# Power.net
KiCad netlist of a schematic drawn in Altium Designer
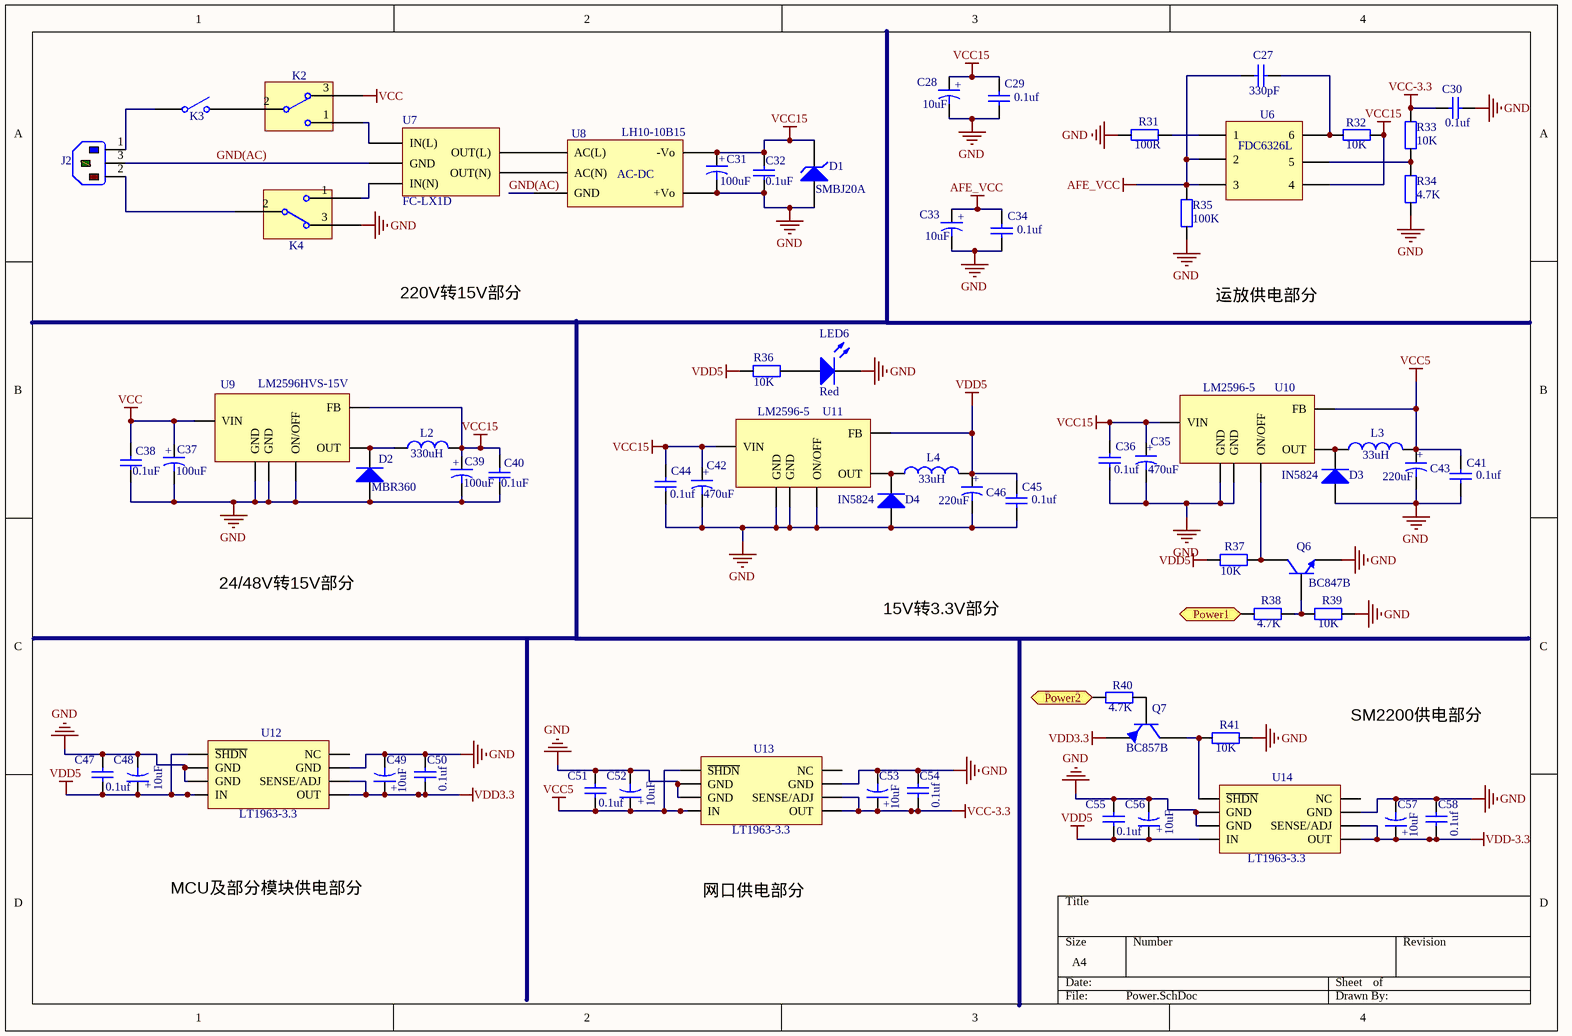
[diagram p0: Power.SchDoc]

(export (version "E")
  (design (tool "Eeschema 10.0.6"))
  (components
    (comp (ref "C27")
      (value "330pF")
      (footprint "0603")
      (fields (field (name "Comment") "Capacitor-0805"))
      (libsource (lib "集成库—大岐") (part "Capacitor-0805"))
    )
    (comp (ref "C28")
      (value "10uF")
      (footprint "3528")
      (fields (field (name "ALTIUM_UNNAMED_1") "+") (field (name "Comment") "电解电容"))
      (libsource (lib "原理图库") (part "电解电容"))
    )
    (comp (ref "C29")
      (value "0.1uf")
      (footprint "0805")
      (fields (field (name "Comment") "Capacitor-0805"))
      (libsource (lib "集成库—大岐") (part "Capacitor-0805"))
    )
    (comp (ref "C30")
      (value "0.1uf")
      (footprint "0603")
      (fields (field (name "Comment") "Capacitor-0805"))
      (libsource (lib "集成库—大岐") (part "Capacitor-0805"))
    )
    (comp (ref "C31")
      (value "100uF")
      (footprint "贴片铝电容-8*10.3")
      (fields (field (name "ALTIUM_UNNAMED_1") "+") (field (name "Comment") "电解电容"))
      (libsource (lib "原理图库") (part "电解电容"))
    )
    (comp (ref "C32")
      (value "0.1uF")
      (footprint "0805")
      (fields (field (name "Comment") "Capacitor-0805"))
      (libsource (lib "原理图库") (part "Capacitor-0805"))
    )
    (comp (ref "C33")
      (value "10uF")
      (footprint "3528")
      (fields (field (name "ALTIUM_UNNAMED_1") "+") (field (name "Comment") "电解电容"))
      (libsource (lib "原理图库") (part "电解电容"))
    )
    (comp (ref "C34")
      (value "0.1uf")
      (footprint "0805")
      (fields (field (name "Comment") "Capacitor-0805"))
      (libsource (lib "集成库—大岐") (part "Capacitor-0805"))
    )
    (comp (ref "C35")
      (value "470uF")
      (footprint "贴片铝电容-10*10")
      (fields (field (name "ALTIUM_UNNAMED_1") "+") (field (name "Comment") "电解电容"))
      (libsource (lib "集成库—大岐") (part "电解电容"))
    )
    (comp (ref "C36")
      (value "0.1uf")
      (footprint "0805")
      (fields (field (name "Comment") "Capacitor-0805"))
      (libsource (lib "集成库—大岐") (part "Capacitor-0805"))
    )
    (comp (ref "C37")
      (value "100uF")
      (footprint "贴片铝电容-8*10.3")
      (fields (field (name "ALTIUM_UNNAMED_1") "+") (field (name "Comment") "电解电容"))
      (libsource (lib "原理图库") (part "电解电容"))
    )
    (comp (ref "C38")
      (value "0.1uF")
      (footprint "0805")
      (fields (field (name "Comment") "Capacitor-0805"))
      (libsource (lib "原理图库") (part "Capacitor-0805"))
    )
    (comp (ref "C39")
      (value "100uF")
      (footprint "贴片铝电容-8*10.3")
      (fields (field (name "ALTIUM_UNNAMED_1") "+") (field (name "Comment") "电解电容"))
      (libsource (lib "原理图库") (part "电解电容"))
    )
    (comp (ref "C40")
      (value "0.1uF")
      (footprint "0805")
      (fields (field (name "Comment") "Capacitor-0805"))
      (libsource (lib "原理图库") (part "Capacitor-0805"))
    )
    (comp (ref "C41")
      (value "0.1uf")
      (footprint "0805")
      (fields (field (name "Comment") "Capacitor-0805"))
      (libsource (lib "集成库—大岐") (part "Capacitor-0805"))
    )
    (comp (ref "C42")
      (value "470uF")
      (footprint "贴片铝电容-10*10")
      (fields (field (name "ALTIUM_UNNAMED_1") "+") (field (name "Comment") "电解电容"))
      (libsource (lib "集成库—大岐") (part "电解电容"))
    )
    (comp (ref "C43")
      (value "220uF")
      (footprint "贴片铝电容-8*10.3")
      (fields (field (name "ALTIUM_UNNAMED_1") "+") (field (name "Comment") "电解电容"))
      (libsource (lib "集成库—大岐") (part "电解电容"))
    )
    (comp (ref "C44")
      (value "0.1uf")
      (footprint "0805")
      (fields (field (name "Comment") "Capacitor-0805"))
      (libsource (lib "集成库—大岐") (part "Capacitor-0805"))
    )
    (comp (ref "C45")
      (value "0.1uf")
      (footprint "0805")
      (fields (field (name "Comment") "Capacitor-0805"))
      (libsource (lib "集成库—大岐") (part "Capacitor-0805"))
    )
    (comp (ref "C46")
      (value "220uF")
      (footprint "贴片铝电容-8*10.3")
      (fields (field (name "ALTIUM_UNNAMED_1") "+") (field (name "Comment") "电解电容"))
      (libsource (lib "集成库—大岐") (part "电解电容"))
    )
    (comp (ref "C47")
      (value "0.1uf")
      (footprint "0805")
      (fields (field (name "Comment") "Capacitor-0805"))
      (libsource (lib "集成库—大岐") (part "Capacitor-0805"))
    )
    (comp (ref "C48")
      (value "10uF")
      (footprint "钽电容1206（A3216）")
      (fields (field (name "ALTIUM_UNNAMED_1") "+") (field (name "Comment") "电解电容"))
      (libsource (lib "集成库—大岐") (part "电解电容"))
    )
    (comp (ref "C49")
      (value "10uF")
      (footprint "钽电容1206（A3216）")
      (fields (field (name "ALTIUM_UNNAMED_1") "+") (field (name "Comment") "电解电容"))
      (libsource (lib "集成库—大岐") (part "电解电容"))
    )
    (comp (ref "C50")
      (value "0.1uf")
      (footprint "0805")
      (fields (field (name "Comment") "Capacitor-0805"))
      (libsource (lib "集成库—大岐") (part "Capacitor-0805"))
    )
    (comp (ref "C51")
      (value "0.1uf")
      (footprint "0805")
      (fields (field (name "Comment") "Capacitor-0805"))
      (libsource (lib "集成库—大岐") (part "Capacitor-0805"))
    )
    (comp (ref "C52")
      (value "10uF")
      (footprint "钽电容1206（A3216）")
      (fields (field (name "ALTIUM_UNNAMED_1") "+") (field (name "Comment") "电解电容"))
      (libsource (lib "集成库—大岐") (part "电解电容"))
    )
    (comp (ref "C53")
      (value "10uF")
      (footprint "钽电容1206（A3216）")
      (fields (field (name "ALTIUM_UNNAMED_1") "+") (field (name "Comment") "电解电容"))
      (libsource (lib "集成库—大岐") (part "电解电容"))
    )
    (comp (ref "C54")
      (value "0.1uf")
      (footprint "0805")
      (fields (field (name "Comment") "Capacitor-0805"))
      (libsource (lib "集成库—大岐") (part "Capacitor-0805"))
    )
    (comp (ref "C55")
      (value "0.1uf")
      (footprint "0805")
      (fields (field (name "Comment") "Capacitor-0805"))
      (libsource (lib "集成库—大岐") (part "Capacitor-0805"))
    )
    (comp (ref "C56")
      (value "10uF")
      (footprint "钽电容1206（A3216）")
      (fields (field (name "ALTIUM_UNNAMED_1") "+") (field (name "Comment") "电解电容"))
      (libsource (lib "集成库—大岐") (part "电解电容"))
    )
    (comp (ref "C57")
      (value "10uF")
      (footprint "钽电容1206（A3216）")
      (fields (field (name "ALTIUM_UNNAMED_1") "+") (field (name "Comment") "电解电容"))
      (libsource (lib "集成库—大岐") (part "电解电容"))
    )
    (comp (ref "C58")
      (value "0.1uf")
      (footprint "0805")
      (fields (field (name "Comment") "Capacitor-0805"))
      (libsource (lib "集成库—大岐") (part "Capacitor-0805"))
    )
    (comp (ref "D1")
      (value "SMBJ20A")
      (footprint "SMBJ20A")
      (fields (field (name "NAME") "SMBJ20A"))
      (libsource (lib "原理图库") (part "SMBJ20A"))
    )
    (comp (ref "D2")
      (value "MBR360")
      (footprint "IN5824")
      (fields (field (name "Comment") "IN5824"))
      (libsource (lib "原理图库") (part "IN5824"))
    )
    (comp (ref "D3")
      (value "IN5824")
      (footprint "IN5824")
      (fields (field (name "ALTIUM_UNNAMED_1") "IN5824"))
      (libsource (lib "集成库—大岐") (part "IN5824"))
    )
    (comp (ref "D4")
      (value "IN5824")
      (footprint "IN5824")
      (fields (field (name "ALTIUM_UNNAMED_1") "IN5824"))
      (libsource (lib "集成库—大岐") (part "IN5824"))
    )
    (comp (ref "J2") (value "三脚航空插头") (footprint "三脚航空插头") (libsource (lib "原理图库") (part "三脚航空插头")))
    (comp (ref "K2") (value "选择开关") (footprint "选择开关") (libsource (lib "") (part "选择开关_1")))
    (comp (ref "K3") (value "开关") (footprint "T型接头") (libsource (lib "原理图库") (part "开关")))
    (comp (ref "K4") (value "选择开关") (footprint "选择开关") (libsource (lib "原理图库") (part "选择开关")))
    (comp (ref "L2")
      (value "330uH")
      (footprint "Inductor(7.8*7*5)")
      (fields (field (name "Comment") "Inductor"))
      (libsource (lib "原理图库") (part "Inductor"))
    )
    (comp (ref "L3")
      (value "33uH")
      (footprint "SLF6025   电感")
      (fields (field (name "Comment") "Inductor"))
      (libsource (lib "集成库—大岐") (part "Inductor"))
    )
    (comp (ref "L4")
      (value "33uH")
      (footprint "SLF6025   电感")
      (fields (field (name "Comment") "Inductor"))
      (libsource (lib "集成库—大岐") (part "Inductor"))
    )
    (comp (ref "LED6")
      (value "LED")
      (footprint "外插小灯")
      (fields (field (name "COLOR") "Red"))
      (libsource (lib "原理图库") (part "LED"))
    )
    (comp (ref "Q6")
      (value "BC847")
      (footprint "BC847B")
      (fields (field (name "NAME") "BC847B"))
      (libsource (lib "原理图库") (part "BC847"))
    )
    (comp (ref "Q7")
      (value "BC587B")
      (footprint "BC847B")
      (fields (field (name "NAME") "BC857B"))
      (libsource (lib "原理图库") (part "BC587B"))
    )
    (comp (ref "R31")
      (value "100R")
      (footprint "0603")
      (fields (field (name "Comment") "Resistor-0603"))
      (libsource (lib "") (part "Resistor-0603_2"))
    )
    (comp (ref "R32")
      (value "10K")
      (footprint "0603")
      (fields (field (name "Comment") "Resistor-0603"))
      (libsource (lib "原理图库") (part "Resistor-0603"))
    )
    (comp (ref "R33")
      (value "10K")
      (footprint "0603")
      (fields (field (name "Comment") "Resistor-0603"))
      (libsource (lib "") (part "Resistor-0603_1"))
    )
    (comp (ref "R34")
      (value "4.7K")
      (footprint "0603")
      (fields (field (name "Comment") "Resistor-0603"))
      (libsource (lib "") (part "Resistor-0603_1"))
    )
    (comp (ref "R35")
      (value "100K")
      (footprint "0603")
      (fields (field (name "Comment") "Resistor-0603"))
      (libsource (lib "") (part "Resistor-0603_1"))
    )
    (comp (ref "R36")
      (value "10K")
      (footprint "0603")
      (fields (field (name "Comment") "Resistor-0603"))
      (libsource (lib "原理图库") (part "Resistor-0603"))
    )
    (comp (ref "R37")
      (value "10K")
      (footprint "0603")
      (fields (field (name "Comment") "Resistor-0603"))
      (libsource (lib "") (part "Resistor-0603_2"))
    )
    (comp (ref "R38")
      (value "4.7K")
      (footprint "0603")
      (fields (field (name "Comment") "Resistor-0603"))
      (libsource (lib "原理图库") (part "Resistor-0603"))
    )
    (comp (ref "R39")
      (value "10K")
      (footprint "0603")
      (fields (field (name "Comment") "Resistor-0603"))
      (libsource (lib "原理图库") (part "Resistor-0603"))
    )
    (comp (ref "R40")
      (value "4.7K")
      (footprint "0603")
      (fields (field (name "Comment") "Resistor-0603"))
      (libsource (lib "原理图库") (part "Resistor-0603"))
    )
    (comp (ref "R41")
      (value "10K")
      (footprint "0603")
      (fields (field (name "Comment") "Resistor-0603"))
      (libsource (lib "原理图库") (part "Resistor-0603"))
    )
    (comp (ref "U6")
      (value "FDC6326L")
      (footprint "FDC6326L")
      (fields (field (name "NAME") "FDC6326L"))
      (libsource (lib "原理图库") (part "FDC6326L"))
    )
    (comp (ref "U7")
      (value "FC-LX1D")
      (footprint "FC-LX1D")
      (fields (field (name "NAME") "FC-LX1D"))
      (libsource (lib "原理图库") (part "FC-LX1D"))
    )
    (comp (ref "U8")
      (value "LH10-10B15")
      (footprint "LH10-10B15")
      (fields (field (name "DESCRIBE") "AC-DC") (field (name "NAME") "LH10-10B15"))
      (libsource (lib "原理图库") (part "LH10-10B15"))
    )
    (comp (ref "U9")
      (value "LM2596HVS-15V")
      (footprint "LM2596")
      (fields (field (name "Comment") "LM2596"))
      (libsource (lib "原理图库") (part "LM2596"))
    )
    (comp (ref "U10")
      (value "LM2596")
      (footprint "LM2596")
      (fields (field (name "ALTIUM_UNNAMED_1") "LM2596-5"))
      (libsource (lib "集成库—大岐") (part "LM2596"))
    )
    (comp (ref "U11")
      (value "LM2596")
      (footprint "LM2596")
      (fields (field (name "ALTIUM_UNNAMED_1") "LM2596-5"))
      (libsource (lib "集成库—大岐") (part "LM2596"))
    )
    (comp (ref "U12")
      (value "LT1963")
      (footprint "LT1963")
      (fields (field (name "ALTIUM_UNNAMED_1") "LT1963-3.3"))
      (libsource (lib "集成库—大岐") (part "LT1963"))
    )
    (comp (ref "U13")
      (value "LT1963")
      (footprint "LT1963")
      (fields (field (name "ALTIUM_UNNAMED_1") "LT1963-3.3"))
      (libsource (lib "集成库—大岐") (part "LT1963"))
    )
    (comp (ref "U14")
      (value "LT1963")
      (footprint "LT1963")
      (fields (field (name "ALTIUM_UNNAMED_1") "LT1963-3.3"))
      (libsource (lib "集成库—大岐") (part "LT1963"))
    )
  )
  (nets
    (net (code "1") (name "/GND(AC)") (class "Default")
      (node (ref "J2") (pin "3") (pinfunction "3_3") (pintype "passive"))
      (node (ref "U7") (pin "1") (pinfunction "GND_1") (pintype "passive"))
      (node (ref "U8") (pin "1") (pinfunction "GND_1") (pintype "passive"))
    )
    (net (code "2") (name "/Power1") (class "Default")
      (node (ref "R38") (pin "2") (pinfunction "2_2") (pintype "passive"))
    )
    (net (code "3") (name "/Power2") (class "Default")
      (node (ref "R40") (pin "2") (pinfunction "2_2") (pintype "passive"))
    )
    (net (code "4") (name "AFE_VCC") (class "Default")
      (node (ref "C27") (pin "2") (pinfunction "2_2") (pintype "passive"))
      (node (ref "C33") (pin "2") (pinfunction "2_2") (pintype "passive"))
      (node (ref "C34") (pin "2") (pinfunction "2_2") (pintype "passive"))
      (node (ref "R35") (pin "2") (pinfunction "2_2") (pintype "passive"))
      (node (ref "U6") (pin "2") (pinfunction "2_2") (pintype "passive"))
      (node (ref "U6") (pin "3") (pinfunction "3_3") (pintype "passive"))
    )
    (net (code "5") (name "GND") (class "Default")
      (node (ref "C28") (pin "1") (pinfunction "1_1") (pintype "passive"))
      (node (ref "C29") (pin "1") (pinfunction "1_1") (pintype "passive"))
      (node (ref "C30") (pin "1") (pinfunction "1_1") (pintype "passive"))
      (node (ref "C31") (pin "1") (pinfunction "1_1") (pintype "passive"))
      (node (ref "C32") (pin "1") (pinfunction "1_1") (pintype "passive"))
      (node (ref "C33") (pin "1") (pinfunction "1_1") (pintype "passive"))
      (node (ref "C34") (pin "1") (pinfunction "1_1") (pintype "passive"))
      (node (ref "C35") (pin "1") (pinfunction "1_1") (pintype "passive"))
      (node (ref "C36") (pin "1") (pinfunction "1_1") (pintype "passive"))
      (node (ref "C37") (pin "1") (pinfunction "1_1") (pintype "passive"))
      (node (ref "C38") (pin "1") (pinfunction "1_1") (pintype "passive"))
      (node (ref "C39") (pin "1") (pinfunction "1_1") (pintype "passive"))
      (node (ref "C40") (pin "1") (pinfunction "1_1") (pintype "passive"))
      (node (ref "C41") (pin "1") (pinfunction "1_1") (pintype "passive"))
      (node (ref "C42") (pin "1") (pinfunction "1_1") (pintype "passive"))
      (node (ref "C43") (pin "1") (pinfunction "1_1") (pintype "passive"))
      (node (ref "C44") (pin "1") (pinfunction "1_1") (pintype "passive"))
      (node (ref "C45") (pin "1") (pinfunction "1_1") (pintype "passive"))
      (node (ref "C46") (pin "1") (pinfunction "1_1") (pintype "passive"))
      (node (ref "C47") (pin "2") (pinfunction "2_2") (pintype "passive"))
      (node (ref "C48") (pin "1") (pinfunction "1_1") (pintype "passive"))
      (node (ref "C49") (pin "1") (pinfunction "1_1") (pintype "passive"))
      (node (ref "C50") (pin "2") (pinfunction "2_2") (pintype "passive"))
      (node (ref "C51") (pin "2") (pinfunction "2_2") (pintype "passive"))
      (node (ref "C52") (pin "1") (pinfunction "1_1") (pintype "passive"))
      (node (ref "C53") (pin "1") (pinfunction "1_1") (pintype "passive"))
      (node (ref "C54") (pin "2") (pinfunction "2_2") (pintype "passive"))
      (node (ref "C55") (pin "2") (pinfunction "2_2") (pintype "passive"))
      (node (ref "C56") (pin "1") (pinfunction "1_1") (pintype "passive"))
      (node (ref "C57") (pin "1") (pinfunction "1_1") (pintype "passive"))
      (node (ref "C58") (pin "2") (pinfunction "2_2") (pintype "passive"))
      (node (ref "D1") (pin "1") (pinfunction "A_1") (pintype "passive"))
      (node (ref "D2") (pin "1") (pinfunction "A_1") (pintype "passive"))
      (node (ref "D3") (pin "1") (pinfunction "A_1") (pintype "passive"))
      (node (ref "D4") (pin "1") (pinfunction "A_1") (pintype "passive"))
      (node (ref "K4") (pin "3") (pinfunction "3_3") (pintype "passive"))
      (node (ref "LED6") (pin "2") (pinfunction "2_2") (pintype "passive"))
      (node (ref "Q6") (pin "1") (pinfunction "E_1") (pintype "passive"))
      (node (ref "R31") (pin "1") (pinfunction "1_1") (pintype "passive"))
      (node (ref "R34") (pin "1") (pinfunction "1_1") (pintype "passive"))
      (node (ref "R35") (pin "1") (pinfunction "1_1") (pintype "passive"))
      (node (ref "R39") (pin "1") (pinfunction "1_1") (pintype "passive"))
      (node (ref "R41") (pin "1") (pinfunction "1_1") (pintype "passive"))
      (node (ref "U10") (pin "3") (pinfunction "GND_3") (pintype "passive"))
      (node (ref "U10") (pin "6") (pinfunction "GND_6") (pintype "passive"))
      (node (ref "U11") (pin "3") (pinfunction "GND_3") (pintype "passive"))
      (node (ref "U11") (pin "5") (pinfunction "ON/OFF_5") (pintype "passive"))
      (node (ref "U11") (pin "6") (pinfunction "GND_6") (pintype "passive"))
      (node (ref "U12") (pin "3") (pinfunction "GND_3") (pintype "passive"))
      (node (ref "U12") (pin "6") (pinfunction "GND_6") (pintype "passive"))
      (node (ref "U12") (pin "7") (pinfunction "GND_7") (pintype "passive"))
      (node (ref "U13") (pin "3") (pinfunction "GND_3") (pintype "passive"))
      (node (ref "U13") (pin "6") (pinfunction "GND_6") (pintype "passive"))
      (node (ref "U13") (pin "7") (pinfunction "GND_7") (pintype "passive"))
      (node (ref "U14") (pin "3") (pinfunction "GND_3") (pintype "passive"))
      (node (ref "U14") (pin "6") (pinfunction "GND_6") (pintype "passive"))
      (node (ref "U14") (pin "7") (pinfunction "GND_7") (pintype "passive"))
      (node (ref "U8") (pin "8") (pinfunction "+Vo_8") (pintype "passive"))
      (node (ref "U9") (pin "3") (pinfunction "GND_3") (pintype "passive"))
      (node (ref "U9") (pin "5") (pinfunction "ON/OFF_5") (pintype "passive"))
      (node (ref "U9") (pin "6") (pinfunction "GND_6") (pintype "passive"))
    )
    (net (code "6") (name "Net-(C27-Pad1)") (class "Default")
      (node (ref "C27") (pin "1") (pinfunction "1_1") (pintype "passive"))
      (node (ref "R32") (pin "2") (pinfunction "2_2") (pintype "passive"))
      (node (ref "U6") (pin "6") (pinfunction "6_6") (pintype "passive"))
    )
    (net (code "7") (name "Net-(D2-K)") (class "Default")
      (node (ref "D2") (pin "2") (pinfunction "K_2") (pintype "passive"))
      (node (ref "L2") (pin "1") (pinfunction "1_1") (pintype "passive"))
      (node (ref "U9") (pin "2") (pinfunction "OUT_2") (pintype "passive"))
    )
    (net (code "8") (name "Net-(D3-K)") (class "Default")
      (node (ref "D3") (pin "2") (pinfunction "K_2") (pintype "passive"))
      (node (ref "L3") (pin "1") (pinfunction "1_1") (pintype "passive"))
      (node (ref "U10") (pin "2") (pinfunction "OUT_2") (pintype "passive"))
    )
    (net (code "9") (name "Net-(D4-K)") (class "Default")
      (node (ref "D4") (pin "2") (pinfunction "K_2") (pintype "passive"))
      (node (ref "L4") (pin "1") (pinfunction "1_1") (pintype "passive"))
      (node (ref "U11") (pin "2") (pinfunction "OUT_2") (pintype "passive"))
    )
    (net (code "10") (name "Net-(J2-Pad2)") (class "Default")
      (node (ref "J2") (pin "2") (pinfunction "2_2") (pintype "passive"))
      (node (ref "K4") (pin "2") (pinfunction "2_2") (pintype "passive"))
    )
    (net (code "11") (name "Net-(K3-COMMON)") (class "Default")
      (node (ref "J2") (pin "1") (pinfunction "1_1") (pintype "passive"))
      (node (ref "K3") (pin "1") (pinfunction "COMMON_1") (pintype "passive"))
    )
    (net (code "12") (name "Net-(K3-NO)") (class "Default")
      (node (ref "K2") (pin "2") (pinfunction "2_2") (pintype "passive"))
      (node (ref "K3") (pin "2") (pinfunction "NO_2") (pintype "passive"))
    )
    (net (code "13") (name "Net-(LED6-A)") (class "Default")
      (node (ref "LED6") (pin "1") (pinfunction "A_1") (pintype "passive"))
      (node (ref "R36") (pin "1") (pinfunction "1_1") (pintype "passive"))
    )
    (net (code "14") (name "Net-(Q6-B)") (class "Default")
      (node (ref "Q6") (pin "2") (pinfunction "B_2") (pintype "passive"))
      (node (ref "R38") (pin "1") (pinfunction "1_1") (pintype "passive"))
      (node (ref "R39") (pin "2") (pinfunction "2_2") (pintype "passive"))
    )
    (net (code "15") (name "Net-(Q6-C)") (class "Default")
      (node (ref "Q6") (pin "3") (pinfunction "C_3") (pintype "passive"))
      (node (ref "R37") (pin "2") (pinfunction "2_2") (pintype "passive"))
      (node (ref "U10") (pin "5") (pinfunction "ON/OFF_5") (pintype "passive"))
    )
    (net (code "16") (name "Net-(Q7-B)") (class "Default")
      (node (ref "Q7") (pin "2") (pinfunction "B_2") (pintype "passive"))
      (node (ref "R40") (pin "1") (pinfunction "1_1") (pintype "passive"))
    )
    (net (code "17") (name "Net-(Q7-C)") (class "Default")
      (node (ref "Q7") (pin "3") (pinfunction "C_3") (pintype "passive"))
      (node (ref "R41") (pin "2") (pinfunction "2_2") (pintype "passive"))
      (node (ref "U14") (pin "5") (pinfunction "~{SHDN}_5") (pintype "passive"))
    )
    (net (code "18") (name "Net-(R31-Pad2)") (class "Default")
      (node (ref "R31") (pin "2") (pinfunction "2_2") (pintype "passive"))
      (node (ref "U6") (pin "1") (pinfunction "1_1") (pintype "passive"))
    )
    (net (code "19") (name "Net-(R33-Pad1)") (class "Default")
      (node (ref "R33") (pin "1") (pinfunction "1_1") (pintype "passive"))
      (node (ref "R34") (pin "2") (pinfunction "2_2") (pintype "passive"))
      (node (ref "U6") (pin "5") (pinfunction "5_5") (pintype "passive"))
    )
    (net (code "20") (name "Net-(U7-IN(L))") (class "Default")
      (node (ref "K2") (pin "1") (pinfunction "1_1") (pintype "passive"))
      (node (ref "U7") (pin "3") (pinfunction "IN(L)_3") (pintype "passive"))
    )
    (net (code "21") (name "Net-(U7-IN(N))") (class "Default")
      (node (ref "K4") (pin "1") (pinfunction "1_1") (pintype "passive"))
      (node (ref "U7") (pin "2") (pinfunction "IN(N)_2") (pintype "passive"))
    )
    (net (code "22") (name "Net-(U7-OUT(L))") (class "Default")
      (node (ref "U7") (pin "4") (pinfunction "OUT(L)_4") (pintype "passive"))
      (node (ref "U8") (pin "3") (pinfunction "AC(L)_3") (pintype "passive"))
    )
    (net (code "23") (name "Net-(U7-OUT(N))") (class "Default")
      (node (ref "U7") (pin "5") (pinfunction "OUT(N)_5") (pintype "passive"))
      (node (ref "U8") (pin "2") (pinfunction "AC(N)_2") (pintype "passive"))
    )
    (net (code "24") (name "VCC") (class "Default")
      (node (ref "C37") (pin "2") (pinfunction "2_2") (pintype "passive"))
      (node (ref "C38") (pin "2") (pinfunction "2_2") (pintype "passive"))
      (node (ref "K2") (pin "3") (pinfunction "3_3") (pintype "passive"))
      (node (ref "U9") (pin "1") (pinfunction "VIN_1") (pintype "passive"))
    )
    (net (code "25") (name "VCC-3.3") (class "Default")
      (node (ref "C30") (pin "2") (pinfunction "2_2") (pintype "passive"))
      (node (ref "C53") (pin "2") (pinfunction "2_2") (pintype "passive"))
      (node (ref "C54") (pin "1") (pinfunction "1_1") (pintype "passive"))
      (node (ref "R33") (pin "2") (pinfunction "2_2") (pintype "passive"))
      (node (ref "U13") (pin "1") (pinfunction "OUT_1") (pintype "passive"))
      (node (ref "U13") (pin "2") (pinfunction "SENSE/ADJ_2") (pintype "passive"))
    )
    (net (code "26") (name "VCC5") (class "Default")
      (node (ref "C41") (pin "2") (pinfunction "2_2") (pintype "passive"))
      (node (ref "C43") (pin "2") (pinfunction "2_2") (pintype "passive"))
      (node (ref "C51") (pin "1") (pinfunction "1_1") (pintype "passive"))
      (node (ref "C52") (pin "2") (pinfunction "2_2") (pintype "passive"))
      (node (ref "L3") (pin "2") (pinfunction "2_2") (pintype "passive"))
      (node (ref "U10") (pin "4") (pinfunction "FB_4") (pintype "passive"))
      (node (ref "U13") (pin "5") (pinfunction "~{SHDN}_5") (pintype "passive"))
      (node (ref "U13") (pin "8") (pinfunction "IN_8") (pintype "passive"))
    )
    (net (code "27") (name "VCC15") (class "Default")
      (node (ref "C28") (pin "2") (pinfunction "2_2") (pintype "passive"))
      (node (ref "C29") (pin "2") (pinfunction "2_2") (pintype "passive"))
      (node (ref "C31") (pin "2") (pinfunction "2_2") (pintype "passive"))
      (node (ref "C32") (pin "2") (pinfunction "2_2") (pintype "passive"))
      (node (ref "C35") (pin "2") (pinfunction "2_2") (pintype "passive"))
      (node (ref "C36") (pin "2") (pinfunction "2_2") (pintype "passive"))
      (node (ref "C39") (pin "2") (pinfunction "2_2") (pintype "passive"))
      (node (ref "C40") (pin "2") (pinfunction "2_2") (pintype "passive"))
      (node (ref "C42") (pin "2") (pinfunction "2_2") (pintype "passive"))
      (node (ref "C44") (pin "2") (pinfunction "2_2") (pintype "passive"))
      (node (ref "D1") (pin "2") (pinfunction "K_2") (pintype "passive"))
      (node (ref "L2") (pin "2") (pinfunction "2_2") (pintype "passive"))
      (node (ref "R32") (pin "1") (pinfunction "1_1") (pintype "passive"))
      (node (ref "U10") (pin "1") (pinfunction "VIN_1") (pintype "passive"))
      (node (ref "U11") (pin "1") (pinfunction "VIN_1") (pintype "passive"))
      (node (ref "U6") (pin "4") (pinfunction "4_4") (pintype "passive"))
      (node (ref "U8") (pin "4") (pinfunction "-Vo_4") (pintype "passive"))
      (node (ref "U9") (pin "4") (pinfunction "FB_4") (pintype "passive"))
    )
    (net (code "28") (name "VDD-3.3") (class "Default")
      (node (ref "C57") (pin "2") (pinfunction "2_2") (pintype "passive"))
      (node (ref "C58") (pin "1") (pinfunction "1_1") (pintype "passive"))
      (node (ref "U14") (pin "1") (pinfunction "OUT_1") (pintype "passive"))
      (node (ref "U14") (pin "2") (pinfunction "SENSE/ADJ_2") (pintype "passive"))
    )
    (net (code "29") (name "VDD3.3") (class "Default")
      (node (ref "C49") (pin "2") (pinfunction "2_2") (pintype "passive"))
      (node (ref "C50") (pin "1") (pinfunction "1_1") (pintype "passive"))
      (node (ref "Q7") (pin "1") (pinfunction "E_1") (pintype "passive"))
      (node (ref "U12") (pin "1") (pinfunction "OUT_1") (pintype "passive"))
      (node (ref "U12") (pin "2") (pinfunction "SENSE/ADJ_2") (pintype "passive"))
    )
    (net (code "30") (name "VDD5") (class "Default")
      (node (ref "C45") (pin "2") (pinfunction "2_2") (pintype "passive"))
      (node (ref "C46") (pin "2") (pinfunction "2_2") (pintype "passive"))
      (node (ref "C47") (pin "1") (pinfunction "1_1") (pintype "passive"))
      (node (ref "C48") (pin "2") (pinfunction "2_2") (pintype "passive"))
      (node (ref "C55") (pin "1") (pinfunction "1_1") (pintype "passive"))
      (node (ref "C56") (pin "2") (pinfunction "2_2") (pintype "passive"))
      (node (ref "L4") (pin "2") (pinfunction "2_2") (pintype "passive"))
      (node (ref "R36") (pin "2") (pinfunction "2_2") (pintype "passive"))
      (node (ref "R37") (pin "1") (pinfunction "1_1") (pintype "passive"))
      (node (ref "U11") (pin "4") (pinfunction "FB_4") (pintype "passive"))
      (node (ref "U12") (pin "5") (pinfunction "~{SHDN}_5") (pintype "passive"))
      (node (ref "U12") (pin "8") (pinfunction "IN_8") (pintype "passive"))
      (node (ref "U14") (pin "8") (pinfunction "IN_8") (pintype "passive"))
    )
    (net (code "31") (name "unconnected-(U12-NC-Pad4)") (class "Default")
      (node (ref "U12") (pin "4") (pinfunction "NC_4") (pintype "passive"))
    )
    (net (code "32") (name "unconnected-(U13-NC-Pad4)") (class "Default")
      (node (ref "U13") (pin "4") (pinfunction "NC_4") (pintype "passive"))
    )
    (net (code "33") (name "unconnected-(U14-NC-Pad4)") (class "Default")
      (node (ref "U14") (pin "4") (pinfunction "NC_4") (pintype "passive"))
    )
  )
)
